# USB_to_UART_With_Zigbee_V1_0.net
KiCad netlist of a schematic drawn in Altium Designer
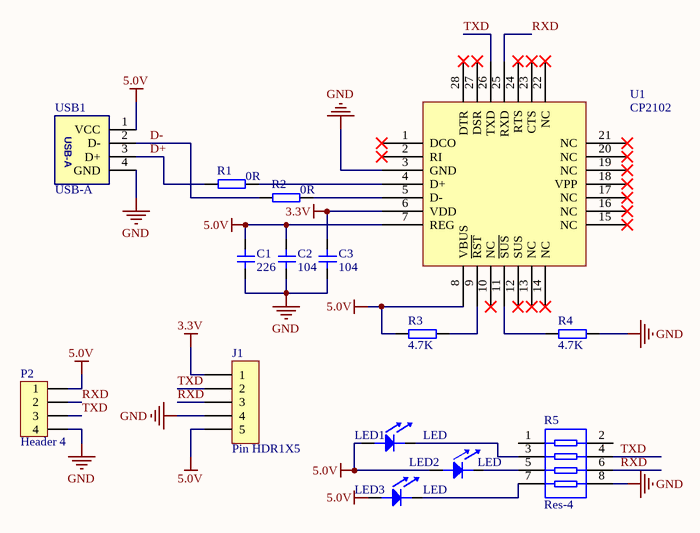
[diagram p0: USB to UART With Zigbee V1.0.SchDoc]

(export (version "E")
  (design (tool "Eeschema 10.0.6"))
  (components
    (comp (ref "C1")
      (value "226")
      (footprint "0805C")
      (description "无极贴片电容")
      (libsource (lib "集大电协2.0") (part "Cap1"))
    )
    (comp (ref "C2")
      (value "104")
      (footprint "0805C")
      (description "无极贴片电容")
      (libsource (lib "集大电协2.0") (part "Cap1"))
    )
    (comp (ref "C3")
      (value "104")
      (footprint "0805C")
      (description "无极贴片电容")
      (libsource (lib "集大电协2.0") (part "Cap1"))
    )
    (comp (ref "J1")
      (value "Pin HDR1X5")
      (footprint "Pin HDR1X5/2mm-W")
      (libsource (lib "排针") (part "Pin HDR1X5"))
    )
    (comp (ref "LED1")
      (value "LED")
      (footprint "0805LED(GREEN)")
      (description "发光二极管")
      (libsource (lib "集大电协2.0") (part "LED"))
    )
    (comp (ref "LED2")
      (value "LED")
      (footprint "0805LED(GREEN)")
      (description "发光二极管")
      (libsource (lib "集大电协2.0") (part "LED"))
    )
    (comp (ref "LED3")
      (value "LED")
      (footprint "0805LED(GREEN)")
      (description "发光二极管")
      (libsource (lib "集大电协2.0") (part "LED"))
    )
    (comp (ref "P2")
      (value "Header 4")
      (footprint "Header 4(排母)")
      (description "排针")
      (libsource (lib "集大电协2.0") (part "Header 4"))
    )
    (comp (ref "R1")
      (value "0R")
      (footprint "0805R")
      (description "电阻")
      (libsource (lib "集大电协2.0") (part "Res"))
    )
    (comp (ref "R2")
      (value "0R")
      (footprint "0805R")
      (description "电阻")
      (libsource (lib "集大电协2.0") (part "Res"))
    )
    (comp (ref "R3")
      (value "4.7K")
      (footprint "0805R")
      (description "电阻")
      (libsource (lib "集大电协2.0") (part "Res"))
    )
    (comp (ref "R4")
      (value "4.7K")
      (footprint "0805R")
      (description "电阻")
      (libsource (lib "集大电协2.0") (part "Res"))
    )
    (comp (ref "R5")
      (value "Res-4")
      (footprint "排阻(4位贴片)")
      (description "排阻")
      (libsource (lib "集大电协2.0") (part "Res-4"))
    )
    (comp (ref "U1")
      (value "CP2102")
      (footprint "QFN-28")
      (description "USB转串口芯片")
      (libsource (lib "集大电协2.0") (part "CP2102"))
    )
    (comp (ref "USB1") (value "USB-A") (footprint "USB_A/P_B") (libsource (lib "USB") (part "USB-A")))
  )
  (nets
    (net (code "1") (name "/D+") (class "Default")
      (node (ref "R1") (pin "1") (pinfunction "1_1") (pintype "passive"))
      (node (ref "USB1") (pin "3") (pinfunction "D+_3") (pintype "passive"))
    )
    (net (code "2") (name "/D-") (class "Default")
      (node (ref "R2") (pin "1") (pinfunction "1_1") (pintype "passive"))
      (node (ref "USB1") (pin "2") (pinfunction "D-_2") (pintype "passive"))
    )
    (net (code "3") (name "/RXD") (class "Default")
      (node (ref "J1") (pin "3") (pinfunction "3_3") (pintype "passive"))
      (node (ref "P2") (pin "2") (pinfunction "2_2") (pintype "passive"))
      (node (ref "R5") (pin "6") (pinfunction "6_6") (pintype "passive"))
      (node (ref "U1") (pin "25") (pinfunction "RXD_25") (pintype "passive"))
    )
    (net (code "4") (name "/TXD") (class "Default")
      (node (ref "J1") (pin "2") (pinfunction "2_2") (pintype "passive"))
      (node (ref "P2") (pin "3") (pinfunction "3_3") (pintype "passive"))
      (node (ref "R5") (pin "4") (pinfunction "4_4") (pintype "passive"))
      (node (ref "U1") (pin "26") (pinfunction "TXD_26") (pintype "passive"))
    )
    (net (code "5") (name "3.3V") (class "Default")
      (node (ref "C3") (pin "2") (pinfunction "2_2") (pintype "passive"))
      (node (ref "J1") (pin "1") (pinfunction "1_1") (pintype "passive"))
      (node (ref "U1") (pin "6") (pinfunction "VDD_6") (pintype "passive"))
    )
    (net (code "6") (name "5.0V") (class "Default")
      (node (ref "C1") (pin "2") (pinfunction "2_2") (pintype "passive"))
      (node (ref "C2") (pin "2") (pinfunction "2_2") (pintype "passive"))
      (node (ref "J1") (pin "5") (pinfunction "5_5") (pintype "passive"))
      (node (ref "LED1") (pin "1") (pintype "passive"))
      (node (ref "LED2") (pin "1") (pintype "passive"))
      (node (ref "LED3") (pin "1") (pintype "passive"))
      (node (ref "P2") (pin "1") (pinfunction "1_1") (pintype "passive"))
      (node (ref "R3") (pin "2") (pinfunction "2_2") (pintype "passive"))
      (node (ref "U1") (pin "7") (pinfunction "REG_7") (pintype "passive"))
      (node (ref "U1") (pin "8") (pinfunction "VBUS_8") (pintype "passive"))
      (node (ref "USB1") (pin "1") (pinfunction "VCC_1") (pintype "passive"))
    )
    (net (code "7") (name "GND") (class "Default")
      (node (ref "C1") (pin "1") (pinfunction "1_1") (pintype "passive"))
      (node (ref "C2") (pin "1") (pinfunction "1_1") (pintype "passive"))
      (node (ref "C3") (pin "1") (pinfunction "1_1") (pintype "passive"))
      (node (ref "J1") (pin "4") (pinfunction "4_4") (pintype "passive"))
      (node (ref "P2") (pin "4") (pinfunction "4_4") (pintype "passive"))
      (node (ref "R4") (pin "1") (pinfunction "1_1") (pintype "passive"))
      (node (ref "R5") (pin "8") (pinfunction "8_8") (pintype "passive"))
      (node (ref "U1") (pin "3") (pinfunction "GND_3") (pintype "passive"))
      (node (ref "USB1") (pin "4") (pinfunction "GND_4") (pintype "passive"))
    )
    (net (code "8") (name "Net-(LED1-Pad2)") (class "Default")
      (node (ref "LED1") (pin "2") (pinfunction "2_2") (pintype "passive"))
      (node (ref "R5") (pin "3") (pinfunction "3_3") (pintype "passive"))
    )
    (net (code "9") (name "Net-(LED2-Pad2)") (class "Default")
      (node (ref "LED2") (pin "2") (pinfunction "2_2") (pintype "passive"))
      (node (ref "R5") (pin "5") (pinfunction "5_5") (pintype "passive"))
    )
    (net (code "10") (name "Net-(LED3-Pad2)") (class "Default")
      (node (ref "LED3") (pin "2") (pinfunction "2_2") (pintype "passive"))
      (node (ref "R5") (pin "7") (pinfunction "7_7") (pintype "passive"))
    )
    (net (code "11") (name "Net-(U1-D+)") (class "Default")
      (node (ref "R1") (pin "2") (pinfunction "2_2") (pintype "passive"))
      (node (ref "U1") (pin "4") (pinfunction "D+_4") (pintype "passive"))
    )
    (net (code "12") (name "Net-(U1-D-)") (class "Default")
      (node (ref "R2") (pin "2") (pinfunction "2_2") (pintype "passive"))
      (node (ref "U1") (pin "5") (pinfunction "D-_5") (pintype "passive"))
    )
    (net (code "13") (name "Net-(U1-~{RST})") (class "Default")
      (node (ref "R3") (pin "1") (pinfunction "1_1") (pintype "passive"))
      (node (ref "U1") (pin "9") (pinfunction "~{RST}_9") (pintype "passive"))
    )
    (net (code "14") (name "Net-(U1-~{SUS})") (class "Default")
      (node (ref "R4") (pin "2") (pinfunction "2_2") (pintype "passive"))
      (node (ref "U1") (pin "11") (pinfunction "~{SUS}_11") (pintype "passive"))
    )
    (net (code "15") (name "unconnected-(R5-Pad1)") (class "Default")
      (node (ref "R5") (pin "1") (pinfunction "1_1") (pintype "passive"))
    )
    (net (code "16") (name "unconnected-(R5-Pad2)") (class "Default")
      (node (ref "R5") (pin "2") (pinfunction "2_2") (pintype "passive"))
    )
    (net (code "17") (name "unconnected-(U1-CTS-Pad23)") (class "Default")
      (node (ref "U1") (pin "23") (pinfunction "CTS_23") (pintype "passive+no_connect"))
    )
    (net (code "18") (name "unconnected-(U1-DCO-Pad1)") (class "Default")
      (node (ref "U1") (pin "1") (pinfunction "DCO_1") (pintype "passive+no_connect"))
    )
    (net (code "19") (name "unconnected-(U1-DSR-Pad27)") (class "Default")
      (node (ref "U1") (pin "27") (pinfunction "DSR_27") (pintype "passive+no_connect"))
    )
    (net (code "20") (name "unconnected-(U1-DTR-Pad28)") (class "Default")
      (node (ref "U1") (pin "28") (pinfunction "DTR_28") (pintype "passive+no_connect"))
    )
    (net (code "21") (name "unconnected-(U1-NC-Pad10)") (class "Default")
      (node (ref "U1") (pin "10") (pinfunction "NC_10") (pintype "passive+no_connect"))
    )
    (net (code "22") (name "unconnected-(U1-NC-Pad13)") (class "Default")
      (node (ref "U1") (pin "13") (pinfunction "NC_13") (pintype "passive+no_connect"))
    )
    (net (code "23") (name "unconnected-(U1-NC-Pad14)") (class "Default")
      (node (ref "U1") (pin "14") (pinfunction "NC_14") (pintype "passive+no_connect"))
    )
    (net (code "24") (name "unconnected-(U1-NC-Pad15)") (class "Default")
      (node (ref "U1") (pin "15") (pinfunction "NC_15") (pintype "passive+no_connect"))
    )
    (net (code "25") (name "unconnected-(U1-NC-Pad16)") (class "Default")
      (node (ref "U1") (pin "16") (pinfunction "NC_16") (pintype "passive+no_connect"))
    )
    (net (code "26") (name "unconnected-(U1-NC-Pad17)") (class "Default")
      (node (ref "U1") (pin "17") (pinfunction "NC_17") (pintype "passive+no_connect"))
    )
    (net (code "27") (name "unconnected-(U1-NC-Pad19)") (class "Default")
      (node (ref "U1") (pin "19") (pinfunction "NC_19") (pintype "passive+no_connect"))
    )
    (net (code "28") (name "unconnected-(U1-NC-Pad20)") (class "Default")
      (node (ref "U1") (pin "20") (pinfunction "NC_20") (pintype "passive+no_connect"))
    )
    (net (code "29") (name "unconnected-(U1-NC-Pad21)") (class "Default")
      (node (ref "U1") (pin "21") (pinfunction "NC_21") (pintype "passive+no_connect"))
    )
    (net (code "30") (name "unconnected-(U1-NC-Pad22)") (class "Default")
      (node (ref "U1") (pin "22") (pinfunction "NC_22") (pintype "passive+no_connect"))
    )
    (net (code "31") (name "unconnected-(U1-RI-Pad2)") (class "Default")
      (node (ref "U1") (pin "2") (pinfunction "RI_2") (pintype "passive+no_connect"))
    )
    (net (code "32") (name "unconnected-(U1-RTS-Pad24)") (class "Default")
      (node (ref "U1") (pin "24") (pinfunction "RTS_24") (pintype "passive+no_connect"))
    )
    (net (code "33") (name "unconnected-(U1-SUS-Pad12)") (class "Default")
      (node (ref "U1") (pin "12") (pinfunction "SUS_12") (pintype "passive+no_connect"))
    )
    (net (code "34") (name "unconnected-(U1-VPP-Pad18)") (class "Default")
      (node (ref "U1") (pin "18") (pinfunction "VPP_18") (pintype "passive+no_connect"))
    )
  )
)
